# Rev1_1.net
KiCad netlist of a schematic drawn in EAGLE
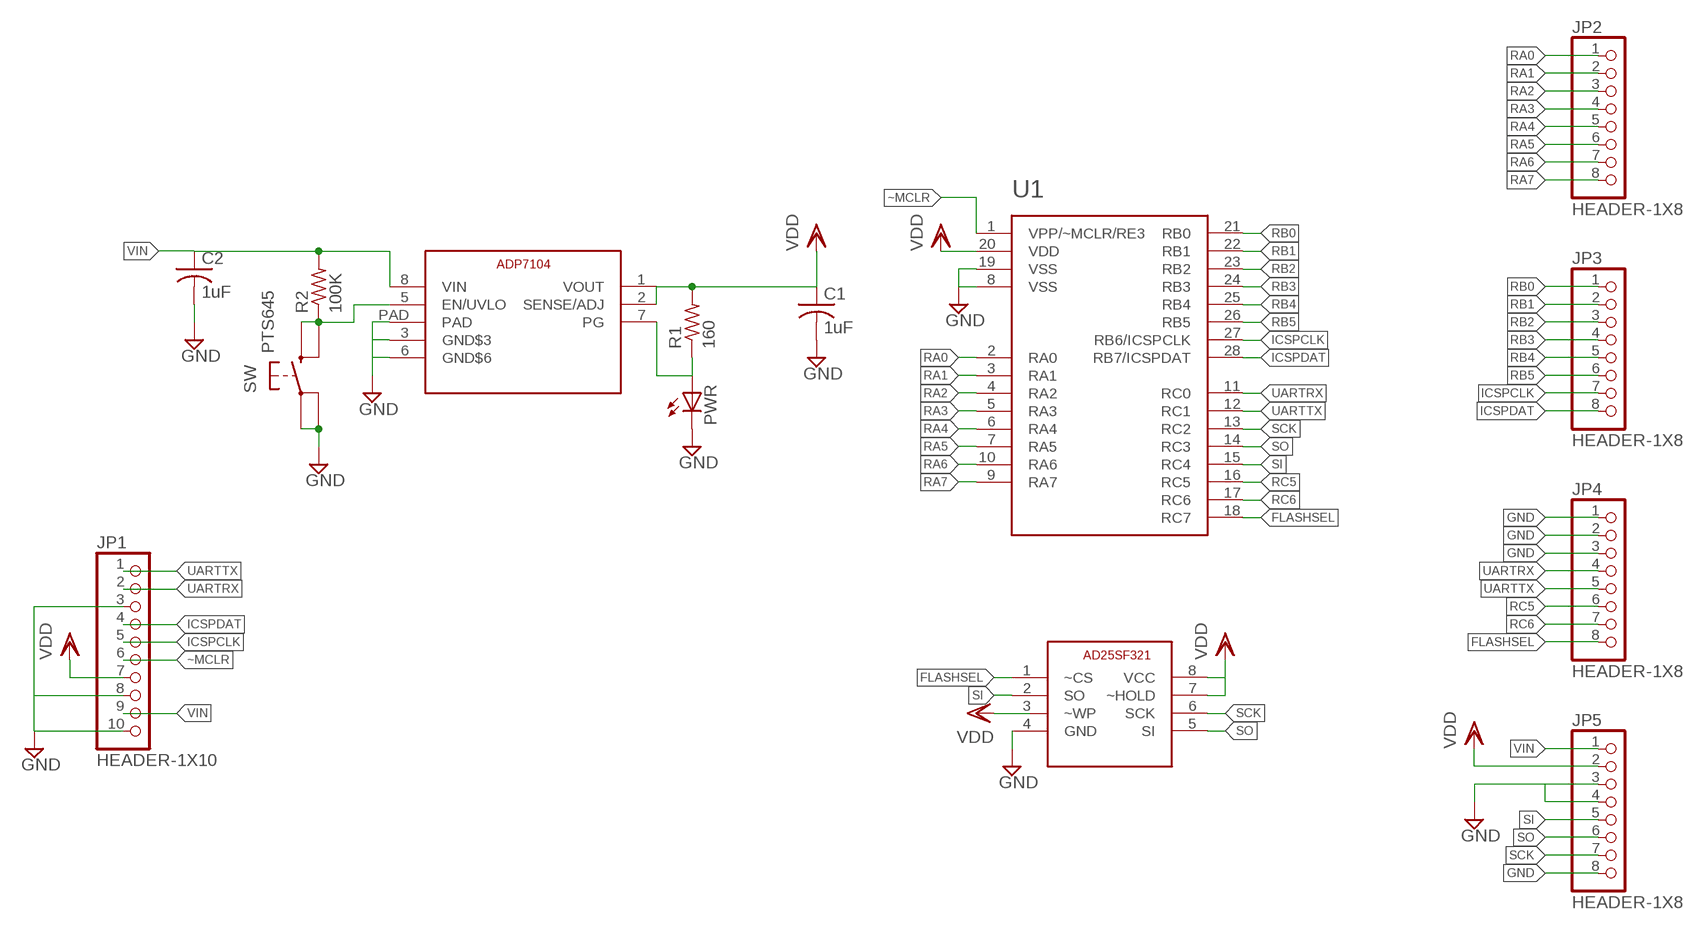
[diagram p0: schematic, sheet 1]

(export (version "E")
  (design (tool "Eeschema 10.0.6"))
  (components
    (comp (ref "C1")
      (value "1uF")
      (footprint "eagle-import:C0805")
      (libsource (lib "eagle-import") (part "C-USC0805"))
    )
    (comp (ref "C2")
      (value "1uF")
      (footprint "eagle-import:C0805")
      (libsource (lib "eagle-import") (part "C-USC0805"))
    )
    (comp (ref "JP1")
      (value "HEADER-1X10")
      (footprint "eagle-import:1X10")
      (libsource (lib "eagle-import") (part "HEADER-1X10"))
    )
    (comp (ref "JP2")
      (value "HEADER-1X8")
      (footprint "eagle-import:1X08")
      (libsource (lib "eagle-import") (part "HEADER-1X8"))
    )
    (comp (ref "JP3")
      (value "HEADER-1X8")
      (footprint "eagle-import:1X08")
      (libsource (lib "eagle-import") (part "HEADER-1X8"))
    )
    (comp (ref "JP4")
      (value "HEADER-1X8")
      (footprint "eagle-import:1X08")
      (libsource (lib "eagle-import") (part "HEADER-1X8"))
    )
    (comp (ref "JP5")
      (value "HEADER-1X8")
      (footprint "eagle-import:1X08")
      (libsource (lib "eagle-import") (part "HEADER-1X8"))
    )
    (comp (ref "PWR")
      (value "LEDCHIP-LED0805")
      (footprint "eagle-import:CHIP-LED0805")
      (libsource (lib "eagle-import") (part "LEDCHIP-LED0805"))
    )
    (comp (ref "R1")
      (value "160")
      (footprint "eagle-import:R0805")
      (libsource (lib "eagle-import") (part "R-US_R0805"))
    )
    (comp (ref "R2")
      (value "100K")
      (footprint "eagle-import:R0805")
      (libsource (lib "eagle-import") (part "R-US_R0805"))
    )
    (comp (ref "SW")
      (value "PTS645")
      (footprint "eagle-import:TSWITCH-6MM")
      (libsource (lib "eagle-import") (part "PTS645"))
    )
    (comp (ref "U1")
      (value "PIC16F1778")
      (footprint "eagle-import:SO28W")
      (libsource (lib "eagle-import") (part "PIC16F1778"))
    )
    (comp (ref "U2")
      (value "AT25SF321")
      (footprint "eagle-import:SOIC8")
      (libsource (lib "eagle-import") (part "AT25SF321"))
    )
    (comp (ref "U3")
      (value "ADP7104")
      (footprint "eagle-import:SOIC8-EXP-PAD")
      (libsource (lib "eagle-import") (part "ADP7104"))
    )
  )
  (nets
    (net (code "1") (name "/~{MCLR}") (class "Default")
      (node (ref "JP1") (pin "6") (pinfunction "6_6") (pintype "passive"))
      (node (ref "U1") (pin "1") (pinfunction "VPP/~{MCLR/RE3}_1") (pintype "bidirectional"))
    )
    (net (code "2") (name "FLASHSEL") (class "Default")
      (node (ref "JP4") (pin "8") (pinfunction "8_8") (pintype "passive"))
      (node (ref "U1") (pin "18") (pinfunction "RC7_18") (pintype "bidirectional"))
      (node (ref "U2") (pin "1") (pinfunction "~{CS}_1") (pintype "bidirectional"))
    )
    (net (code "3") (name "GND") (class "Default")
      (node (ref "C1") (pin "2") (pinfunction "2_2") (pintype "passive"))
      (node (ref "C2") (pin "2") (pinfunction "2_2") (pintype "passive"))
      (node (ref "JP1") (pin "10") (pinfunction "10_10") (pintype "passive"))
      (node (ref "JP1") (pin "3") (pinfunction "3_3") (pintype "passive"))
      (node (ref "JP1") (pin "8") (pinfunction "8_8") (pintype "passive"))
      (node (ref "JP4") (pin "1") (pinfunction "1_1") (pintype "passive"))
      (node (ref "JP4") (pin "2") (pinfunction "2_2") (pintype "passive"))
      (node (ref "JP4") (pin "3") (pinfunction "3_3") (pintype "passive"))
      (node (ref "JP5") (pin "3") (pinfunction "3_3") (pintype "passive"))
      (node (ref "JP5") (pin "4") (pinfunction "4_4") (pintype "passive"))
      (node (ref "JP5") (pin "8") (pinfunction "8_8") (pintype "passive"))
      (node (ref "PWR") (pin "C") (pinfunction "C_C") (pintype "passive"))
      (node (ref "SW") (pin "P$1") (pinfunction "P$1_P$1") (pintype "bidirectional"))
      (node (ref "SW") (pin "P$2") (pinfunction "P$2_P$2") (pintype "bidirectional"))
      (node (ref "U1") (pin "19") (pinfunction "VSS_19") (pintype "bidirectional"))
      (node (ref "U1") (pin "8") (pinfunction "VSS_8") (pintype "bidirectional"))
      (node (ref "U2") (pin "4") (pinfunction "GND_4") (pintype "bidirectional"))
      (node (ref "U3") (pin "3") (pinfunction "GND$3_3") (pintype "bidirectional"))
      (node (ref "U3") (pin "6") (pinfunction "GND$6_6") (pintype "bidirectional"))
      (node (ref "U3") (pin "PAD") (pinfunction "PAD_PAD") (pintype "bidirectional"))
    )
    (net (code "4") (name "ICSPCLK") (class "Default")
      (node (ref "JP1") (pin "5") (pinfunction "5_5") (pintype "passive"))
      (node (ref "JP3") (pin "7") (pinfunction "7_7") (pintype "passive"))
      (node (ref "U1") (pin "27") (pinfunction "RB6/ICSPCLK_27") (pintype "bidirectional"))
    )
    (net (code "5") (name "ICSPDAT") (class "Default")
      (node (ref "JP1") (pin "4") (pinfunction "4_4") (pintype "passive"))
      (node (ref "JP3") (pin "8") (pinfunction "8_8") (pintype "passive"))
      (node (ref "U1") (pin "28") (pinfunction "RB7/ICSPDAT_28") (pintype "bidirectional"))
    )
    (net (code "6") (name "Net-(U3-EN{slash}UVLO)") (class "Default")
      (node (ref "R2") (pin "1") (pinfunction "1_1") (pintype "passive"))
      (node (ref "SW") (pin "P$3") (pinfunction "P$3_P$3") (pintype "bidirectional"))
      (node (ref "SW") (pin "P$4") (pinfunction "P$4_P$4") (pintype "bidirectional"))
      (node (ref "U3") (pin "5") (pinfunction "EN/UVLO_5") (pintype "bidirectional"))
    )
    (net (code "7") (name "Net-(U3-PG)") (class "Default")
      (node (ref "PWR") (pin "A") (pinfunction "A_A") (pintype "passive"))
      (node (ref "R1") (pin "1") (pinfunction "1_1") (pintype "passive"))
      (node (ref "U3") (pin "7") (pinfunction "PG_7") (pintype "bidirectional"))
    )
    (net (code "8") (name "RA0") (class "Default")
      (node (ref "JP2") (pin "1") (pinfunction "1_1") (pintype "passive"))
      (node (ref "U1") (pin "2") (pinfunction "RA0_2") (pintype "bidirectional"))
    )
    (net (code "9") (name "RA1") (class "Default")
      (node (ref "JP2") (pin "2") (pinfunction "2_2") (pintype "passive"))
      (node (ref "U1") (pin "3") (pinfunction "RA1_3") (pintype "bidirectional"))
    )
    (net (code "10") (name "RA2") (class "Default")
      (node (ref "JP2") (pin "3") (pinfunction "3_3") (pintype "passive"))
      (node (ref "U1") (pin "4") (pinfunction "RA2_4") (pintype "bidirectional"))
    )
    (net (code "11") (name "RA3") (class "Default")
      (node (ref "JP2") (pin "4") (pinfunction "4_4") (pintype "passive"))
      (node (ref "U1") (pin "5") (pinfunction "RA3_5") (pintype "bidirectional"))
    )
    (net (code "12") (name "RA4") (class "Default")
      (node (ref "JP2") (pin "5") (pinfunction "5_5") (pintype "passive"))
      (node (ref "U1") (pin "6") (pinfunction "RA4_6") (pintype "bidirectional"))
    )
    (net (code "13") (name "RA5") (class "Default")
      (node (ref "JP2") (pin "6") (pinfunction "6_6") (pintype "passive"))
      (node (ref "U1") (pin "7") (pinfunction "RA5_7") (pintype "bidirectional"))
    )
    (net (code "14") (name "RA6") (class "Default")
      (node (ref "JP2") (pin "7") (pinfunction "7_7") (pintype "passive"))
      (node (ref "U1") (pin "10") (pinfunction "RA6_10") (pintype "bidirectional"))
    )
    (net (code "15") (name "RA7") (class "Default")
      (node (ref "JP2") (pin "8") (pinfunction "8_8") (pintype "passive"))
      (node (ref "U1") (pin "9") (pinfunction "RA7_9") (pintype "bidirectional"))
    )
    (net (code "16") (name "RB0") (class "Default")
      (node (ref "JP3") (pin "1") (pinfunction "1_1") (pintype "passive"))
      (node (ref "U1") (pin "21") (pinfunction "RB0_21") (pintype "bidirectional"))
    )
    (net (code "17") (name "RB1") (class "Default")
      (node (ref "JP3") (pin "2") (pinfunction "2_2") (pintype "passive"))
      (node (ref "U1") (pin "22") (pinfunction "RB1_22") (pintype "bidirectional"))
    )
    (net (code "18") (name "RB2") (class "Default")
      (node (ref "JP3") (pin "3") (pinfunction "3_3") (pintype "passive"))
      (node (ref "U1") (pin "23") (pinfunction "RB2_23") (pintype "bidirectional"))
    )
    (net (code "19") (name "RB3") (class "Default")
      (node (ref "JP3") (pin "4") (pinfunction "4_4") (pintype "passive"))
      (node (ref "U1") (pin "24") (pinfunction "RB3_24") (pintype "bidirectional"))
    )
    (net (code "20") (name "RB4") (class "Default")
      (node (ref "JP3") (pin "5") (pinfunction "5_5") (pintype "passive"))
      (node (ref "U1") (pin "25") (pinfunction "RB4_25") (pintype "bidirectional"))
    )
    (net (code "21") (name "RB5") (class "Default")
      (node (ref "JP3") (pin "6") (pinfunction "6_6") (pintype "passive"))
      (node (ref "U1") (pin "26") (pinfunction "RB5_26") (pintype "bidirectional"))
    )
    (net (code "22") (name "RC5") (class "Default")
      (node (ref "JP4") (pin "6") (pinfunction "6_6") (pintype "passive"))
      (node (ref "U1") (pin "16") (pinfunction "RC5_16") (pintype "bidirectional"))
    )
    (net (code "23") (name "RC6") (class "Default")
      (node (ref "JP4") (pin "7") (pinfunction "7_7") (pintype "passive"))
      (node (ref "U1") (pin "17") (pinfunction "RC6_17") (pintype "bidirectional"))
    )
    (net (code "24") (name "SCK") (class "Default")
      (node (ref "JP5") (pin "7") (pinfunction "7_7") (pintype "passive"))
      (node (ref "U1") (pin "13") (pinfunction "RC2_13") (pintype "bidirectional"))
      (node (ref "U2") (pin "6") (pinfunction "SCK_6") (pintype "bidirectional"))
    )
    (net (code "25") (name "SI") (class "Default")
      (node (ref "JP5") (pin "5") (pinfunction "5_5") (pintype "passive"))
      (node (ref "U1") (pin "15") (pinfunction "RC4_15") (pintype "bidirectional"))
      (node (ref "U2") (pin "2") (pinfunction "SO_2") (pintype "bidirectional"))
    )
    (net (code "26") (name "SO") (class "Default")
      (node (ref "JP5") (pin "6") (pinfunction "6_6") (pintype "passive"))
      (node (ref "U1") (pin "14") (pinfunction "RC3_14") (pintype "bidirectional"))
      (node (ref "U2") (pin "5") (pinfunction "SI_5") (pintype "bidirectional"))
    )
    (net (code "27") (name "UARTRX") (class "Default")
      (node (ref "JP1") (pin "2") (pinfunction "2_2") (pintype "passive"))
      (node (ref "JP4") (pin "4") (pinfunction "4_4") (pintype "passive"))
      (node (ref "U1") (pin "11") (pinfunction "RC0_11") (pintype "bidirectional"))
    )
    (net (code "28") (name "UARTTX") (class "Default")
      (node (ref "JP1") (pin "1") (pinfunction "1_1") (pintype "passive"))
      (node (ref "JP4") (pin "5") (pinfunction "5_5") (pintype "passive"))
      (node (ref "U1") (pin "12") (pinfunction "RC1_12") (pintype "bidirectional"))
    )
    (net (code "29") (name "VDD") (class "Default")
      (node (ref "C1") (pin "1") (pinfunction "1_1") (pintype "passive"))
      (node (ref "JP1") (pin "7") (pinfunction "7_7") (pintype "passive"))
      (node (ref "JP5") (pin "2") (pinfunction "2_2") (pintype "passive"))
      (node (ref "R1") (pin "2") (pinfunction "2_2") (pintype "passive"))
      (node (ref "U1") (pin "20") (pinfunction "VDD_20") (pintype "bidirectional"))
      (node (ref "U2") (pin "7") (pinfunction "~{HOLD}_7") (pintype "bidirectional"))
      (node (ref "U2") (pin "8") (pinfunction "VCC_8") (pintype "bidirectional"))
      (node (ref "U3") (pin "1") (pinfunction "VOUT_1") (pintype "bidirectional"))
      (node (ref "U3") (pin "2") (pinfunction "SENSE/ADJ_2") (pintype "bidirectional"))
    )
    (net (code "30") (name "VIN") (class "Default")
      (node (ref "C2") (pin "1") (pinfunction "1_1") (pintype "passive"))
      (node (ref "JP1") (pin "9") (pinfunction "9_9") (pintype "passive"))
      (node (ref "JP5") (pin "1") (pinfunction "1_1") (pintype "passive"))
      (node (ref "R2") (pin "2") (pinfunction "2_2") (pintype "passive"))
      (node (ref "U3") (pin "8") (pinfunction "VIN_8") (pintype "bidirectional"))
    )
    (net (code "31") (name "unconnected-(U2-~{WP}-Pad3)") (class "Default")
      (node (ref "U2") (pin "3") (pinfunction "~{WP}_3") (pintype "bidirectional"))
    )
  )
)
